# 7_5G.net
KiCad netlist of a schematic drawn in Altium Designer
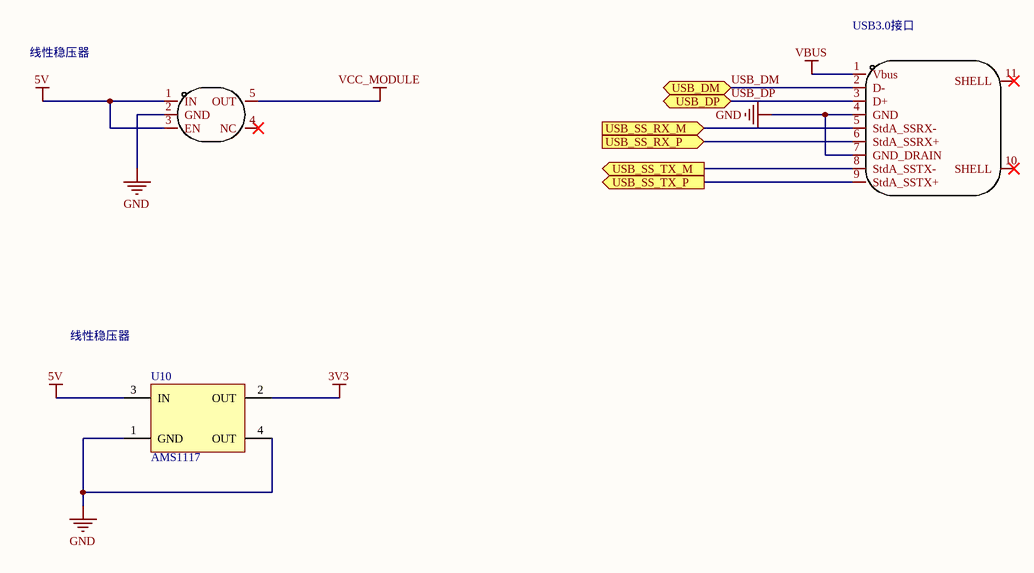
[diagram p0: 7_5G模块电源.SchDoc]

(export (version "E")
  (design (tool "Eeschema 10.0.6"))
  (components
    (comp (ref "U9")
      (value "TLV70237DBVR")
      (footprint "SOT-23-5_L2.9-W1.6-P0.95-LS2.8-BR")
      (libsource (lib "TLV70237DBVR1_TLV70237DBVR.schdoc") (part "TLV70237DBVR"))
    )
    (comp (ref "U10")
      (value "AMS1117")
      (footprint "SOT223_4")
      (libsource (lib "MyComponents_v2.5") (part "AMS1117"))
    )
    (comp (ref "USB3")
      (value "HC-ST-003-01-J")
      (footprint "USB-3.0-A-TH_HC-ST-003-01-Z")
      (libsource (lib "USB_3.0") (part "HC-ST-003-01-J"))
    )
  )
  (nets
    (net (code "1") (name "/USB_DM") (class "Default")
      (node (ref "USB3") (pin "2") (pinfunction "D-_2") (pintype "passive"))
    )
    (net (code "2") (name "/USB_DP") (class "Default")
      (node (ref "USB3") (pin "3") (pinfunction "D+_3") (pintype "passive"))
    )
    (net (code "3") (name "/USB_SS_RX_M") (class "Default")
      (node (ref "USB3") (pin "5") (pinfunction "StdA_SSRX-_5") (pintype "passive"))
    )
    (net (code "4") (name "/USB_SS_RX_P") (class "Default")
      (node (ref "USB3") (pin "6") (pinfunction "StdA_SSRX+_6") (pintype "passive"))
    )
    (net (code "5") (name "/USB_SS_TX_M") (class "Default")
      (node (ref "USB3") (pin "8") (pinfunction "StdA_SSTX-_8") (pintype "passive"))
    )
    (net (code "6") (name "/USB_SS_TX_P") (class "Default")
      (node (ref "USB3") (pin "9") (pinfunction "StdA_SSTX+_9") (pintype "passive"))
    )
    (net (code "7") (name "3V3") (class "Default")
      (node (ref "U10") (pin "2") (pinfunction "OUT_2") (pintype "passive"))
    )
    (net (code "8") (name "5V") (class "Default")
      (node (ref "U10") (pin "3") (pinfunction "IN_3") (pintype "passive"))
      (node (ref "U9") (pin "1") (pinfunction "IN_1") (pintype "passive"))
      (node (ref "U9") (pin "3") (pinfunction "EN_3") (pintype "passive"))
    )
    (net (code "9") (name "GND") (class "Default")
      (node (ref "U10") (pin "1") (pinfunction "GND_1") (pintype "passive"))
      (node (ref "U10") (pin "4") (pinfunction "OUT_4") (pintype "passive"))
      (node (ref "U9") (pin "2") (pinfunction "GND_2") (pintype "passive"))
      (node (ref "USB3") (pin "4") (pinfunction "GND_4") (pintype "passive"))
      (node (ref "USB3") (pin "7") (pinfunction "GND_DRAIN_7") (pintype "passive"))
    )
    (net (code "10") (name "VBUS") (class "Default")
      (node (ref "USB3") (pin "1") (pinfunction "Vbus_1") (pintype "passive"))
    )
    (net (code "11") (name "VCC_MODULE") (class "Default")
      (node (ref "U9") (pin "5") (pinfunction "OUT_5") (pintype "passive"))
    )
    (net (code "12") (name "unconnected-(U9-NC-Pad4)") (class "Default")
      (node (ref "U9") (pin "4") (pinfunction "NC_4") (pintype "passive+no_connect"))
    )
    (net (code "13") (name "unconnected-(USB3-SHELL-Pad10)") (class "Default")
      (node (ref "USB3") (pin "10") (pinfunction "SHELL_10") (pintype "passive+no_connect"))
    )
    (net (code "14") (name "unconnected-(USB3-SHELL-Pad11)") (class "Default")
      (node (ref "USB3") (pin "11") (pinfunction "SHELL_11") (pintype "passive+no_connect"))
    )
  )
)
